# Sound_Sensor_Schematic_Rev1.net
KiCad netlist of a schematic drawn in EAGLE
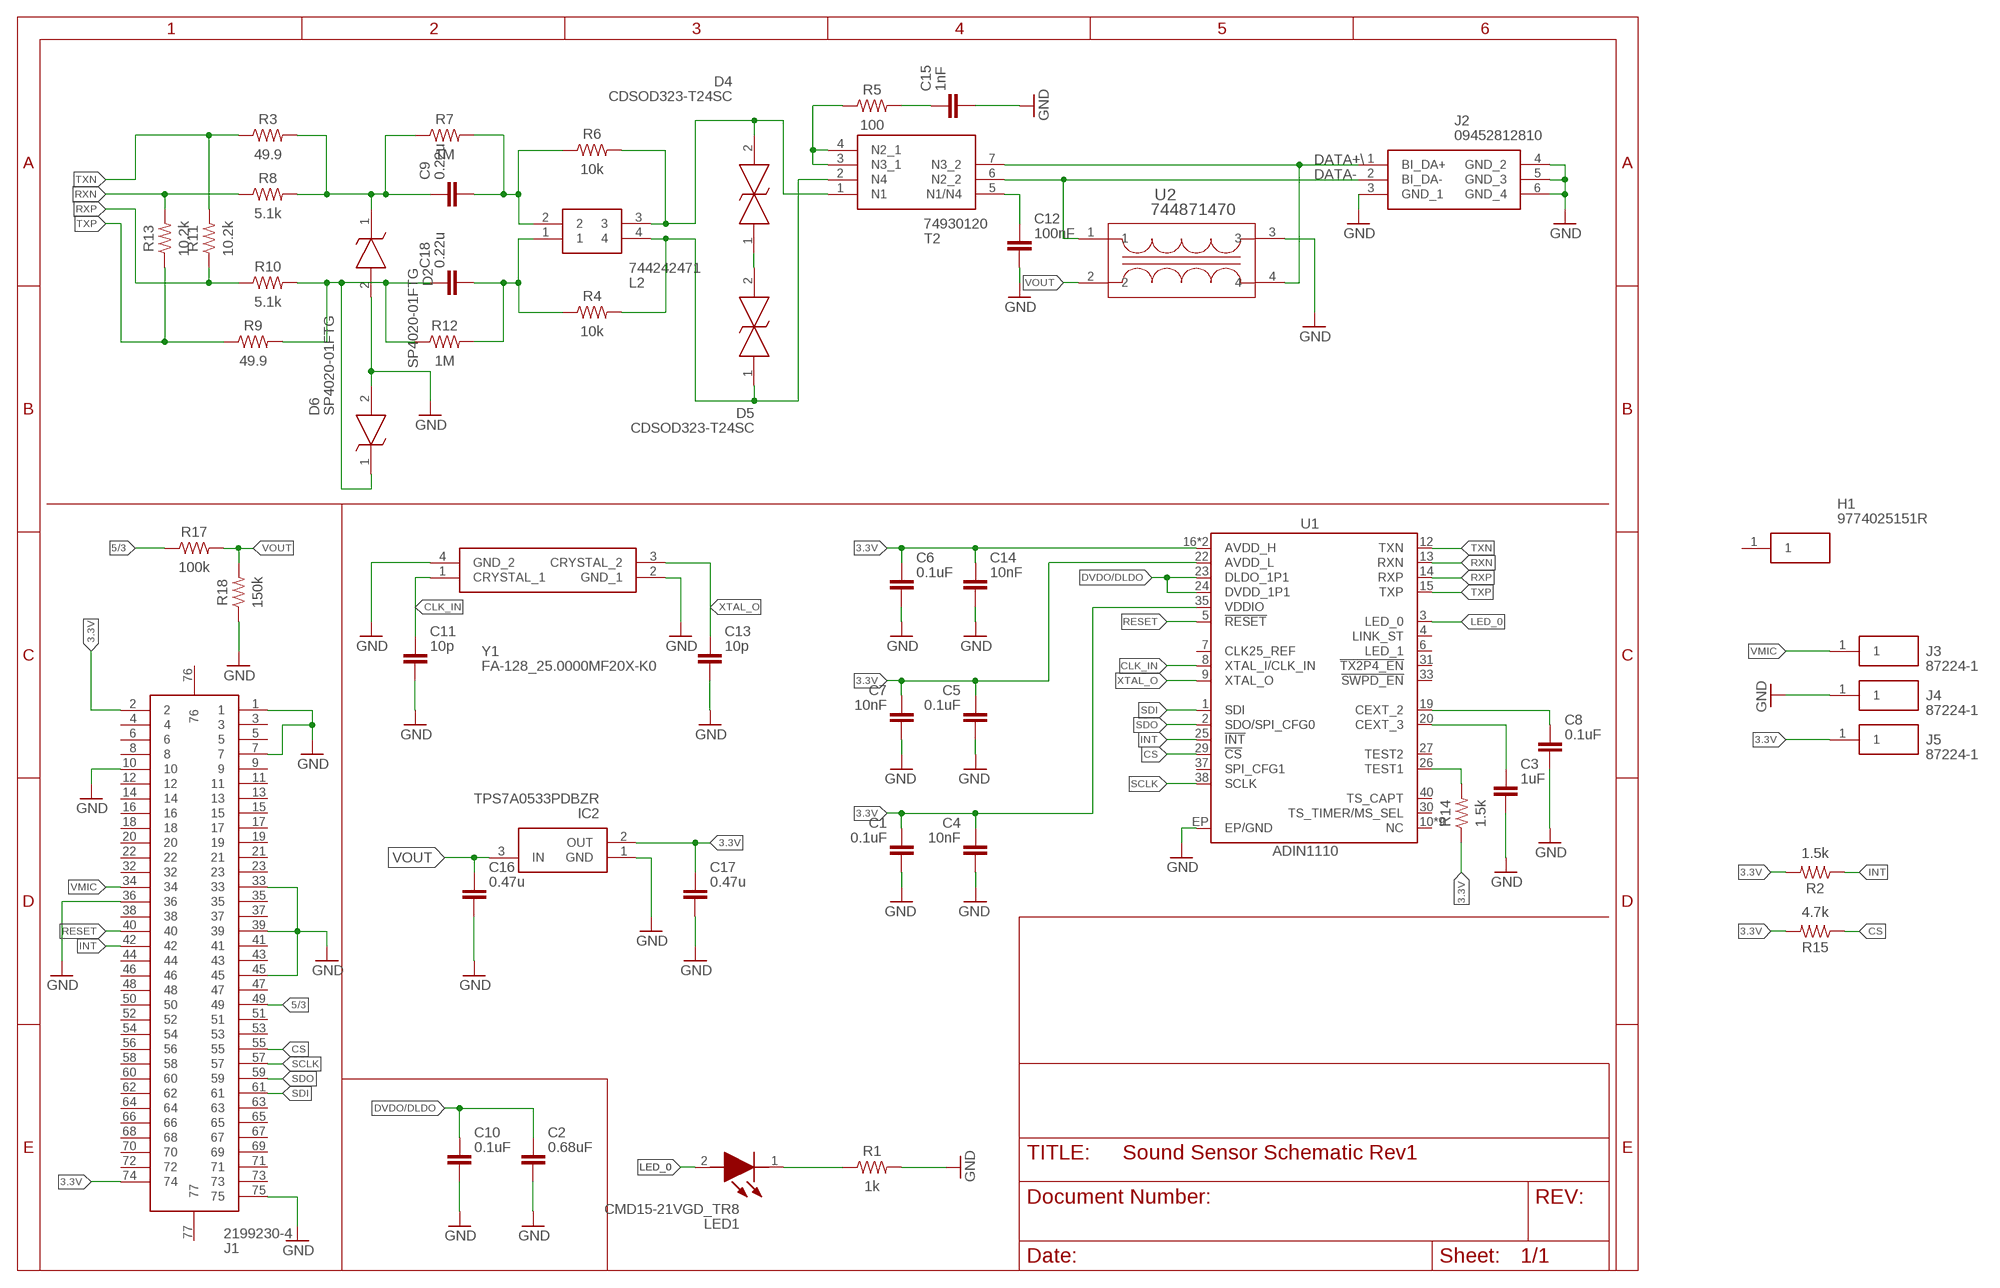
[diagram p0: schematic, sheet 1]

(export (version "E")
  (design (tool "Eeschema 10.0.6"))
  (components
    (comp (ref "C1")
      (value "0.1uF")
      (footprint "eagle-import:CAPC1005X60")
      (libsource (lib "eagle-import") (part "CCHIP-0402(1005-METRIC)_"))
    )
    (comp (ref "C2")
      (value "0.68uF")
      (footprint "eagle-import:CAPC1005X60")
      (libsource (lib "eagle-import") (part "CCHIP-0402(1005-METRIC)_"))
    )
    (comp (ref "C3")
      (value "1uF")
      (footprint "eagle-import:CAPC1005X60")
      (libsource (lib "eagle-import") (part "CCHIP-0402(1005-METRIC)_"))
    )
    (comp (ref "C4")
      (value "10nF")
      (footprint "eagle-import:CAPC1005X60")
      (libsource (lib "eagle-import") (part "CCHIP-0402(1005-METRIC)_"))
    )
    (comp (ref "C5")
      (value "0.1uF")
      (footprint "eagle-import:CAPC1005X60")
      (libsource (lib "eagle-import") (part "CCHIP-0402(1005-METRIC)_"))
    )
    (comp (ref "C6")
      (value "0.1uF")
      (footprint "eagle-import:CAPC1005X60")
      (libsource (lib "eagle-import") (part "CCHIP-0402(1005-METRIC)_"))
    )
    (comp (ref "C7")
      (value "10nF")
      (footprint "eagle-import:CAPC1005X60")
      (libsource (lib "eagle-import") (part "CCHIP-0402(1005-METRIC)_"))
    )
    (comp (ref "C8")
      (value "0.1uF")
      (footprint "eagle-import:CAPC1005X60")
      (libsource (lib "eagle-import") (part "CCHIP-0402(1005-METRIC)_"))
    )
    (comp (ref "C9")
      (value "0.22u")
      (footprint "eagle-import:CAPC1005X60")
      (libsource (lib "eagle-import") (part "CCHIP-0402(1005-METRIC)_"))
    )
    (comp (ref "C10")
      (value "0.1uF")
      (footprint "eagle-import:CAPC1005X60")
      (libsource (lib "eagle-import") (part "CCHIP-0402(1005-METRIC)_"))
    )
    (comp (ref "C11")
      (value "10p")
      (footprint "eagle-import:CAPC1005X60")
      (libsource (lib "eagle-import") (part "CCHIP-0402(1005-METRIC)_"))
    )
    (comp (ref "C12")
      (value "100nF")
      (footprint "eagle-import:CAPC1005X60")
      (libsource (lib "eagle-import") (part "CCHIP-0402(1005-METRIC)_"))
    )
    (comp (ref "C13")
      (value "10p")
      (footprint "eagle-import:CAPC1005X60")
      (libsource (lib "eagle-import") (part "CCHIP-0402(1005-METRIC)_"))
    )
    (comp (ref "C14")
      (value "10nF")
      (footprint "eagle-import:CAPC1005X60")
      (libsource (lib "eagle-import") (part "CCHIP-0402(1005-METRIC)_"))
    )
    (comp (ref "C15")
      (value "1nF")
      (footprint "eagle-import:CAPC1005X60")
      (libsource (lib "eagle-import") (part "CCHIP-0402(1005-METRIC)_"))
    )
    (comp (ref "C16")
      (value "0.47u")
      (footprint "eagle-import:CAPC1005X60")
      (libsource (lib "eagle-import") (part "CCHIP-0402(1005-METRIC)_"))
    )
    (comp (ref "C17")
      (value "0.47u")
      (footprint "eagle-import:CAPC1005X60")
      (libsource (lib "eagle-import") (part "CCHIP-0402(1005-METRIC)_"))
    )
    (comp (ref "C18")
      (value "0.22u")
      (footprint "eagle-import:CAPC1005X60")
      (libsource (lib "eagle-import") (part "CCHIP-0402(1005-METRIC)_"))
    )
    (comp (ref "D2")
      (value "SP4020-01FTG")
      (footprint "eagle-import:SOD2613X114N")
      (fields (field (name "MOUSER_PART_NUMBER") "576-SP4020-01FTG"))
      (libsource (lib "eagle-import") (part "SP4020-01FTG"))
    )
    (comp (ref "D4")
      (value "CDSOD323-T24SC")
      (footprint "eagle-import:SOD2513X114N")
      (fields (field (name "MOUSER_PART_NUMBER") "652-CDSOD323-T24SC"))
      (libsource (lib "eagle-import") (part "CDSOD323-T24SC"))
    )
    (comp (ref "D5")
      (value "CDSOD323-T24SC")
      (footprint "eagle-import:SOD2513X114N")
      (fields (field (name "MOUSER_PART_NUMBER") "652-CDSOD323-T24SC"))
      (libsource (lib "eagle-import") (part "CDSOD323-T24SC"))
    )
    (comp (ref "D6")
      (value "SP4020-01FTG")
      (footprint "eagle-import:SOD2613X114N")
      (fields (field (name "MOUSER_PART_NUMBER") "576-SP4020-01FTG"))
      (libsource (lib "eagle-import") (part "SP4020-01FTG"))
    )
    (comp (ref "H1")
      (value "9774025151R")
      (footprint "eagle-import:9774025151R")
      (fields (field (name "MOUSER_PART_NUMBER") "710-9774025151R"))
      (libsource (lib "eagle-import") (part "9774025151R"))
    )
    (comp (ref "IC2")
      (value "TPS7A0533PDBZR")
      (footprint "eagle-import:SOT95P237X112-3N")
      (fields (field (name "MOUSER_PART_NUMBER") "595-TPS7A0533PDBZR"))
      (libsource (lib "eagle-import") (part "TPS7A0533PDBZR"))
    )
    (comp (ref "J1")
      (value "2199230-4")
      (footprint "eagle-import:21992304")
      (fields (field (name "MOUSER_PART_NUMBER") "571-2199230-4"))
      (libsource (lib "eagle-import") (part "2199230-4"))
    )
    (comp (ref "J2")
      (value "09452812810")
      (footprint "eagle-import:09452812810")
      (fields (field (name "MOUSER_PART_NUMBER") "617-09452812810"))
      (libsource (lib "eagle-import") (part "09452812810"))
    )
    (comp (ref "J3")
      (value "87224-1")
      (footprint "eagle-import:HDRV1W66P0X254_1X1_213X254X107")
      (fields (field (name "MOUSER_PART_NUMBER") "571-872241"))
      (libsource (lib "eagle-import") (part "87224-1"))
    )
    (comp (ref "J4")
      (value "87224-1")
      (footprint "eagle-import:HDRV1W66P0X254_1X1_213X254X107")
      (fields (field (name "MOUSER_PART_NUMBER") "571-872241"))
      (libsource (lib "eagle-import") (part "87224-1"))
    )
    (comp (ref "J5")
      (value "87224-1")
      (footprint "eagle-import:HDRV1W66P0X254_1X1_213X254X107")
      (fields (field (name "MOUSER_PART_NUMBER") "571-872241"))
      (libsource (lib "eagle-import") (part "87224-1"))
    )
    (comp (ref "L2")
      (value "744242471")
      (footprint "eagle-import:744242471")
      (fields (field (name "MOUSER_PART_NUMBER") "710-744242471"))
      (libsource (lib "eagle-import") (part "744242471"))
    )
    (comp (ref "LED1")
      (value "CMD15-21VGD_TR8")
      (footprint "eagle-import:LEDC3215X130N")
      (fields
        (field (name "ARROW_PART_NUMBER") "CMD15-21VGD/TR8")
        (field (name "MOUSER_PART_NUMBER") "606-CMD15-21VGD/TR8")
      )
      (libsource (lib "eagle-import") (part "CMD15-21VGD_TR8"))
    )
    (comp (ref "R1")
      (value "1k")
      (footprint "eagle-import:RESC1005X40")
      (libsource (lib "eagle-import") (part "R-USCHIP-0402(1005-METRIC)_"))
    )
    (comp (ref "R2")
      (value "1.5k")
      (footprint "eagle-import:RESC1005X40")
      (libsource (lib "eagle-import") (part "R-USCHIP-0402(1005-METRIC)_"))
    )
    (comp (ref "R3")
      (value "49.9")
      (footprint "eagle-import:RESC1005X40")
      (libsource (lib "eagle-import") (part "R-USCHIP-0402(1005-METRIC)_"))
    )
    (comp (ref "R4")
      (value "10k")
      (footprint "eagle-import:RESC1005X40")
      (libsource (lib "eagle-import") (part "R-USCHIP-0402(1005-METRIC)_"))
    )
    (comp (ref "R5")
      (value "100")
      (footprint "eagle-import:RESC1005X40")
      (libsource (lib "eagle-import") (part "R-USCHIP-0402(1005-METRIC)_"))
    )
    (comp (ref "R6")
      (value "10k")
      (footprint "eagle-import:RESC1005X40")
      (libsource (lib "eagle-import") (part "R-USCHIP-0402(1005-METRIC)_"))
    )
    (comp (ref "R7")
      (value "1M")
      (footprint "eagle-import:RESC1005X40")
      (libsource (lib "eagle-import") (part "R-USCHIP-0402(1005-METRIC)_"))
    )
    (comp (ref "R8")
      (value "5.1k")
      (footprint "eagle-import:RESC1005X40")
      (libsource (lib "eagle-import") (part "R-USCHIP-0402(1005-METRIC)_"))
    )
    (comp (ref "R9")
      (value "49.9")
      (footprint "eagle-import:RESC1005X40")
      (libsource (lib "eagle-import") (part "R-USCHIP-0402(1005-METRIC)_"))
    )
    (comp (ref "R10")
      (value "5.1k")
      (footprint "eagle-import:RESC1005X40")
      (libsource (lib "eagle-import") (part "R-USCHIP-0402(1005-METRIC)_"))
    )
    (comp (ref "R11")
      (value "10.2k")
      (footprint "eagle-import:RESC1005X40")
      (libsource (lib "eagle-import") (part "R-USCHIP-0402(1005-METRIC)_"))
    )
    (comp (ref "R12")
      (value "1M")
      (footprint "eagle-import:RESC1005X40")
      (libsource (lib "eagle-import") (part "R-USCHIP-0402(1005-METRIC)_"))
    )
    (comp (ref "R13")
      (value "10.2k")
      (footprint "eagle-import:RESC1005X40")
      (libsource (lib "eagle-import") (part "R-USCHIP-0402(1005-METRIC)_"))
    )
    (comp (ref "R14")
      (value "1.5k")
      (footprint "eagle-import:RESC1005X40")
      (libsource (lib "eagle-import") (part "R-USCHIP-0402(1005-METRIC)_"))
    )
    (comp (ref "R15")
      (value "4.7k")
      (footprint "eagle-import:RESC1005X40")
      (libsource (lib "eagle-import") (part "R-USCHIP-0402(1005-METRIC)_"))
    )
    (comp (ref "R17")
      (value "100k")
      (footprint "eagle-import:RESC1005X40")
      (libsource (lib "eagle-import") (part "R-USCHIP-0402(1005-METRIC)_"))
    )
    (comp (ref "R18")
      (value "150k")
      (footprint "eagle-import:RESC1005X40")
      (libsource (lib "eagle-import") (part "R-USCHIP-0402(1005-METRIC)_"))
    )
    (comp (ref "T2")
      (value "74930120")
      (footprint "eagle-import:74930120")
      (fields (field (name "MOUSER_PART_NUMBER") "710-74930120"))
      (libsource (lib "eagle-import") (part "74930120"))
    )
    (comp (ref "U1")
      (value "ADIN1110")
      (footprint "eagle-import:LFCSP-40")
      (libsource (lib "eagle-import") (part "ADIN1110"))
    )
    (comp (ref "U2")
      (value "744871470")
      (footprint "eagle-import:SMT_871470_WRE")
      (fields (field (name "COPYRIGHT") "Copyright (C) 2023 Ultra Librarian. All rights reserved."))
      (libsource (lib "eagle-import") (part "744871470"))
    )
    (comp (ref "Y1")
      (value "FA-128_25.0000MF20X-K0")
      (footprint "eagle-import:FA128250000MF20XK0")
      (fields
        (field (name "MANUFACTURER_PART_NUMBER") "FA-128 25.0000MF20X-K0")
        (field (name "MOUSER_PART_NUMBER") "732-FA-12825F20X-K0")
      )
      (libsource (lib "eagle-import") (part "FA-128_25.0000MF20X-K0"))
    )
  )
  (nets
    (net (code "1") (name "/DATA+\\") (class "Default")
      (node (ref "J2") (pin "1") (pinfunction "BI_DA+_1") (pintype "bidirectional"))
      (node (ref "T2") (pin "7") (pinfunction "N3_2_7") (pintype "bidirectional"))
      (node (ref "U2") (pin "4") (pinfunction "4_4") (pintype "passive"))
    )
    (net (code "2") (name "/DATA-") (class "Default")
      (node (ref "J2") (pin "2") (pinfunction "BI_DA-_2") (pintype "bidirectional"))
      (node (ref "T2") (pin "6") (pinfunction "N2_2_6") (pintype "bidirectional"))
      (node (ref "U2") (pin "1") (pinfunction "1_1") (pintype "passive"))
    )
    (net (code "3") (name "3.3V") (class "Default")
      (node (ref "C1") (pin "1") (pinfunction "1_1") (pintype "passive"))
      (node (ref "C14") (pin "1") (pinfunction "1_1") (pintype "passive"))
      (node (ref "C17") (pin "1") (pinfunction "1_1") (pintype "passive"))
      (node (ref "C4") (pin "1") (pinfunction "1_1") (pintype "passive"))
      (node (ref "C5") (pin "1") (pinfunction "1_1") (pintype "passive"))
      (node (ref "C6") (pin "1") (pinfunction "1_1") (pintype "passive"))
      (node (ref "C7") (pin "1") (pinfunction "1_1") (pintype "passive"))
      (node (ref "IC2") (pin "2") (pinfunction "OUT_2") (pintype "output"))
      (node (ref "J1") (pin "2") (pinfunction "2_2") (pintype "bidirectional"))
      (node (ref "J1") (pin "74") (pinfunction "74_74") (pintype "bidirectional"))
      (node (ref "J5") (pin "1") (pinfunction "1_1") (pintype "bidirectional"))
      (node (ref "R14") (pin "1") (pinfunction "1_1") (pintype "passive"))
      (node (ref "R15") (pin "2") (pinfunction "2_2") (pintype "passive"))
      (node (ref "R2") (pin "2") (pinfunction "2_2") (pintype "passive"))
      (node (ref "U1") (pin "16") (pinfunction "AVDD_H_16") (pintype "bidirectional"))
      (node (ref "U1") (pin "17") (pinfunction "AVDD_H_17") (pintype "bidirectional"))
      (node (ref "U1") (pin "22") (pinfunction "AVDD_L_22") (pintype "bidirectional"))
      (node (ref "U1") (pin "35") (pinfunction "VDDIO_35") (pintype "bidirectional"))
    )
    (net (code "4") (name "5{slash}3") (class "Default")
      (node (ref "J1") (pin "49") (pinfunction "49_49") (pintype "bidirectional"))
      (node (ref "R17") (pin "1") (pinfunction "1_1") (pintype "passive"))
    )
    (net (code "5") (name "CLK_IN") (class "Default")
      (node (ref "C11") (pin "1") (pinfunction "1_1") (pintype "passive"))
      (node (ref "U1") (pin "8") (pinfunction "XTAL_I/CLK_IN_8") (pintype "bidirectional"))
      (node (ref "Y1") (pin "1") (pinfunction "CRYSTAL_1_1") (pintype "bidirectional"))
    )
    (net (code "6") (name "CS") (class "Default")
      (node (ref "J1") (pin "55") (pinfunction "55_55") (pintype "bidirectional"))
      (node (ref "R15") (pin "1") (pinfunction "1_1") (pintype "passive"))
      (node (ref "U1") (pin "29") (pinfunction "~{CS}_29") (pintype "bidirectional"))
    )
    (net (code "7") (name "DVDO{slash}DLDO") (class "Default")
      (node (ref "C10") (pin "1") (pinfunction "1_1") (pintype "passive"))
      (node (ref "C2") (pin "1") (pinfunction "1_1") (pintype "passive"))
      (node (ref "U1") (pin "23") (pinfunction "DLDO_1P1_23") (pintype "bidirectional"))
      (node (ref "U1") (pin "24") (pinfunction "DVDD_1P1_24") (pintype "bidirectional"))
    )
    (net (code "8") (name "GND") (class "Default")
      (node (ref "C1") (pin "2") (pinfunction "2_2") (pintype "passive"))
      (node (ref "C10") (pin "2") (pinfunction "2_2") (pintype "passive"))
      (node (ref "C11") (pin "2") (pinfunction "2_2") (pintype "passive"))
      (node (ref "C12") (pin "2") (pinfunction "2_2") (pintype "passive"))
      (node (ref "C13") (pin "2") (pinfunction "2_2") (pintype "passive"))
      (node (ref "C14") (pin "2") (pinfunction "2_2") (pintype "passive"))
      (node (ref "C15") (pin "2") (pinfunction "2_2") (pintype "passive"))
      (node (ref "C16") (pin "2") (pinfunction "2_2") (pintype "passive"))
      (node (ref "C17") (pin "2") (pinfunction "2_2") (pintype "passive"))
      (node (ref "C2") (pin "2") (pinfunction "2_2") (pintype "passive"))
      (node (ref "C3") (pin "2") (pinfunction "2_2") (pintype "passive"))
      (node (ref "C4") (pin "2") (pinfunction "2_2") (pintype "passive"))
      (node (ref "C5") (pin "2") (pinfunction "2_2") (pintype "passive"))
      (node (ref "C6") (pin "2") (pinfunction "2_2") (pintype "passive"))
      (node (ref "C7") (pin "2") (pinfunction "2_2") (pintype "passive"))
      (node (ref "C8") (pin "2") (pinfunction "2_2") (pintype "passive"))
      (node (ref "D2") (pin "2") (pinfunction "A_2") (pintype "bidirectional"))
      (node (ref "D6") (pin "2") (pinfunction "A_2") (pintype "bidirectional"))
      (node (ref "IC2") (pin "1") (pinfunction "GND_1") (pintype "power_in"))
      (node (ref "J1") (pin "1") (pinfunction "1_1") (pintype "bidirectional"))
      (node (ref "J1") (pin "10") (pinfunction "10_10") (pintype "bidirectional"))
      (node (ref "J1") (pin "33") (pinfunction "33_33") (pintype "bidirectional"))
      (node (ref "J1") (pin "36") (pinfunction "36_36") (pintype "bidirectional"))
      (node (ref "J1") (pin "39") (pinfunction "39_39") (pintype "bidirectional"))
      (node (ref "J1") (pin "45") (pinfunction "45_45") (pintype "bidirectional"))
      (node (ref "J1") (pin "7") (pinfunction "7_7") (pintype "bidirectional"))
      (node (ref "J1") (pin "75") (pinfunction "75_75") (pintype "bidirectional"))
      (node (ref "J2") (pin "3") (pinfunction "GND_1_3") (pintype "bidirectional"))
      (node (ref "J2") (pin "4") (pinfunction "GND_2_4") (pintype "bidirectional"))
      (node (ref "J2") (pin "5") (pinfunction "GND_3_5") (pintype "bidirectional"))
      (node (ref "J2") (pin "6") (pinfunction "GND_4_6") (pintype "bidirectional"))
      (node (ref "J4") (pin "1") (pinfunction "1_1") (pintype "bidirectional"))
      (node (ref "R1") (pin "2") (pinfunction "2_2") (pintype "passive"))
      (node (ref "R18") (pin "1") (pinfunction "1_1") (pintype "passive"))
      (node (ref "U1") (pin "EP") (pinfunction "EP/GND_EP") (pintype "bidirectional"))
      (node (ref "U2") (pin "3") (pinfunction "3_3") (pintype "passive"))
      (node (ref "Y1") (pin "2") (pinfunction "GND_1_2") (pintype "bidirectional"))
      (node (ref "Y1") (pin "4") (pinfunction "GND_2_4") (pintype "bidirectional"))
    )
    (net (code "9") (name "INT") (class "Default")
      (node (ref "J1") (pin "42") (pinfunction "42_42") (pintype "bidirectional"))
      (node (ref "R2") (pin "1") (pinfunction "1_1") (pintype "passive"))
      (node (ref "U1") (pin "25") (pinfunction "~{INT}_25") (pintype "bidirectional"))
    )
    (net (code "10") (name "LED_0") (class "Default")
      (node (ref "LED1") (pin "2") (pinfunction "A_2") (pintype "bidirectional"))
      (node (ref "U1") (pin "3") (pinfunction "LED_0_3") (pintype "bidirectional"))
    )
    (net (code "11") (name "Net-(C9-Pad2)") (class "Default")
      (node (ref "C9") (pin "2") (pinfunction "2_2") (pintype "passive"))
      (node (ref "L2") (pin "2") (pinfunction "2_2") (pintype "bidirectional"))
      (node (ref "R6") (pin "1") (pinfunction "1_1") (pintype "passive"))
      (node (ref "R7") (pin "2") (pinfunction "2_2") (pintype "passive"))
    )
    (net (code "12") (name "Net-(C15-Pad1)") (class "Default")
      (node (ref "C15") (pin "1") (pinfunction "1_1") (pintype "passive"))
      (node (ref "R5") (pin "2") (pinfunction "2_2") (pintype "passive"))
    )
    (net (code "13") (name "Net-(C18-Pad2)") (class "Default")
      (node (ref "C18") (pin "2") (pinfunction "2_2") (pintype "passive"))
      (node (ref "L2") (pin "1") (pinfunction "1_1") (pintype "bidirectional"))
      (node (ref "R12") (pin "2") (pinfunction "2_2") (pintype "passive"))
      (node (ref "R4") (pin "1") (pinfunction "1_1") (pintype "passive"))
    )
    (net (code "14") (name "Net-(D2-K)") (class "Default")
      (node (ref "C9") (pin "1") (pinfunction "1_1") (pintype "passive"))
      (node (ref "D2") (pin "1") (pinfunction "K_1") (pintype "bidirectional"))
      (node (ref "R3") (pin "2") (pinfunction "2_2") (pintype "passive"))
      (node (ref "R7") (pin "1") (pinfunction "1_1") (pintype "passive"))
      (node (ref "R8") (pin "2") (pinfunction "2_2") (pintype "passive"))
    )
    (net (code "15") (name "Net-(D4-Pad1)") (class "Default")
      (node (ref "D4") (pin "1") (pinfunction "1_1") (pintype "bidirectional"))
      (node (ref "D5") (pin "2") (pinfunction "2_2") (pintype "bidirectional"))
    )
    (net (code "16") (name "Net-(D6-K)") (class "Default")
      (node (ref "C18") (pin "1") (pinfunction "1_1") (pintype "passive"))
      (node (ref "D6") (pin "1") (pinfunction "K_1") (pintype "bidirectional"))
      (node (ref "R10") (pin "2") (pinfunction "2_2") (pintype "passive"))
      (node (ref "R12") (pin "1") (pinfunction "1_1") (pintype "passive"))
      (node (ref "R9") (pin "2") (pinfunction "2_2") (pintype "passive"))
    )
    (net (code "17") (name "Net-(LED1-K)") (class "Default")
      (node (ref "LED1") (pin "1") (pinfunction "K_1") (pintype "bidirectional"))
      (node (ref "R1") (pin "1") (pinfunction "1_1") (pintype "passive"))
    )
    (net (code "18") (name "Net-(T2-N1)") (class "Default")
      (node (ref "D4") (pin "2") (pinfunction "2_2") (pintype "bidirectional"))
      (node (ref "L2") (pin "3") (pinfunction "3_3") (pintype "bidirectional"))
      (node (ref "R6") (pin "2") (pinfunction "2_2") (pintype "passive"))
      (node (ref "T2") (pin "1") (pinfunction "N1_1") (pintype "bidirectional"))
    )
    (net (code "19") (name "Net-(T2-N1{slash}N4)") (class "Default")
      (node (ref "C12") (pin "1") (pinfunction "1_1") (pintype "passive"))
      (node (ref "T2") (pin "5") (pinfunction "N1/N4_5") (pintype "bidirectional"))
    )
    (net (code "20") (name "Net-(T2-N2_1)") (class "Default")
      (node (ref "R5") (pin "1") (pinfunction "1_1") (pintype "passive"))
      (node (ref "T2") (pin "3") (pinfunction "N3_1_3") (pintype "bidirectional"))
      (node (ref "T2") (pin "4") (pinfunction "N2_1_4") (pintype "bidirectional"))
    )
    (net (code "21") (name "Net-(T2-N4)") (class "Default")
      (node (ref "D5") (pin "1") (pinfunction "1_1") (pintype "bidirectional"))
      (node (ref "L2") (pin "4") (pinfunction "4_4") (pintype "bidirectional"))
      (node (ref "R4") (pin "2") (pinfunction "2_2") (pintype "passive"))
      (node (ref "T2") (pin "2") (pinfunction "N4_2") (pintype "bidirectional"))
    )
    (net (code "22") (name "Net-(U1-CEXT_2)") (class "Default")
      (node (ref "C8") (pin "1") (pinfunction "1_1") (pintype "passive"))
      (node (ref "U1") (pin "19") (pinfunction "CEXT_2_19") (pintype "bidirectional"))
    )
    (net (code "23") (name "Net-(U1-CEXT_3)") (class "Default")
      (node (ref "C3") (pin "1") (pinfunction "1_1") (pintype "passive"))
      (node (ref "U1") (pin "20") (pinfunction "CEXT_3_20") (pintype "bidirectional"))
    )
    (net (code "24") (name "Net-(U1-TEST1)") (class "Default")
      (node (ref "R14") (pin "2") (pinfunction "2_2") (pintype "passive"))
      (node (ref "U1") (pin "26") (pinfunction "TEST1_26") (pintype "bidirectional"))
    )
    (net (code "25") (name "RESET") (class "Default")
      (node (ref "J1") (pin "40") (pinfunction "40_40") (pintype "bidirectional"))
      (node (ref "U1") (pin "5") (pinfunction "~{RESET}_5") (pintype "bidirectional"))
    )
    (net (code "26") (name "RXN") (class "Default")
      (node (ref "R13") (pin "2") (pinfunction "2_2") (pintype "passive"))
      (node (ref "R8") (pin "1") (pinfunction "1_1") (pintype "passive"))
      (node (ref "U1") (pin "13") (pinfunction "RXN_13") (pintype "bidirectional"))
    )
    (net (code "27") (name "RXP") (class "Default")
      (node (ref "R10") (pin "1") (pinfunction "1_1") (pintype "passive"))
      (node (ref "R11") (pin "1") (pinfunction "1_1") (pintype "passive"))
      (node (ref "U1") (pin "14") (pinfunction "RXP_14") (pintype "bidirectional"))
    )
    (net (code "28") (name "SCLK") (class "Default")
      (node (ref "J1") (pin "57") (pinfunction "57_57") (pintype "bidirectional"))
      (node (ref "U1") (pin "38") (pinfunction "SCLK_38") (pintype "bidirectional"))
    )
    (net (code "29") (name "SDI") (class "Default")
      (node (ref "J1") (pin "61") (pinfunction "61_61") (pintype "bidirectional"))
      (node (ref "U1") (pin "1") (pinfunction "SDI_1") (pintype "bidirectional"))
    )
    (net (code "30") (name "SDO") (class "Default")
      (node (ref "J1") (pin "59") (pinfunction "59_59") (pintype "bidirectional"))
      (node (ref "U1") (pin "2") (pinfunction "SDO/SPI_CFG0_2") (pintype "bidirectional"))
    )
    (net (code "31") (name "TXN") (class "Default")
      (node (ref "R11") (pin "2") (pinfunction "2_2") (pintype "passive"))
      (node (ref "R3") (pin "1") (pinfunction "1_1") (pintype "passive"))
      (node (ref "U1") (pin "12") (pinfunction "TXN_12") (pintype "bidirectional"))
    )
    (net (code "32") (name "TXP") (class "Default")
      (node (ref "R13") (pin "1") (pinfunction "1_1") (pintype "passive"))
      (node (ref "R9") (pin "1") (pinfunction "1_1") (pintype "passive"))
      (node (ref "U1") (pin "15") (pinfunction "TXP_15") (pintype "bidirectional"))
    )
    (net (code "33") (name "VMIC") (class "Default")
      (node (ref "J1") (pin "34") (pinfunction "34_34") (pintype "bidirectional"))
      (node (ref "J3") (pin "1") (pinfunction "1_1") (pintype "bidirectional"))
    )
    (net (code "34") (name "VOUT") (class "Default")
      (node (ref "C16") (pin "1") (pinfunction "1_1") (pintype "passive"))
      (node (ref "IC2") (pin "3") (pinfunction "IN_3") (pintype "input"))
      (node (ref "R17") (pin "2") (pinfunction "2_2") (pintype "passive"))
      (node (ref "R18") (pin "2") (pinfunction "2_2") (pintype "passive"))
      (node (ref "U2") (pin "2") (pinfunction "2_2") (pintype "passive"))
    )
    (net (code "35") (name "XTAL_O") (class "Default")
      (node (ref "C13") (pin "1") (pinfunction "1_1") (pintype "passive"))
      (node (ref "U1") (pin "9") (pinfunction "XTAL_O_9") (pintype "bidirectional"))
      (node (ref "Y1") (pin "3") (pinfunction "CRYSTAL_2_3") (pintype "bidirectional"))
    )
    (net (code "36") (name "unconnected-(H1-Pad1)") (class "Default")
      (node (ref "H1") (pin "1") (pinfunction "1_1") (pintype "bidirectional"))
    )
    (net (code "37") (name "unconnected-(J1-Pad3)") (class "Default")
      (node (ref "J1") (pin "3") (pinfunction "3_3") (pintype "bidirectional"))
    )
    (net (code "38") (name "unconnected-(J1-Pad4)") (class "Default")
      (node (ref "J1") (pin "4") (pinfunction "4_4") (pintype "bidirectional"))
    )
    (net (code "39") (name "unconnected-(J1-Pad5)") (class "Default")
      (node (ref "J1") (pin "5") (pinfunction "5_5") (pintype "bidirectional"))
    )
    (net (code "40") (name "unconnected-(J1-Pad6)") (class "Default")
      (node (ref "J1") (pin "6") (pinfunction "6_6") (pintype "bidirectional"))
    )
    (net (code "41") (name "unconnected-(J1-Pad8)") (class "Default")
      (node (ref "J1") (pin "8") (pinfunction "8_8") (pintype "bidirectional"))
    )
    (net (code "42") (name "unconnected-(J1-Pad9)") (class "Default")
      (node (ref "J1") (pin "9") (pinfunction "9_9") (pintype "bidirectional"))
    )
    (net (code "43") (name "unconnected-(J1-Pad11)") (class "Default")
      (node (ref "J1") (pin "11") (pinfunction "11_11") (pintype "bidirectional"))
    )
    (net (code "44") (name "unconnected-(J1-Pad12)") (class "Default")
      (node (ref "J1") (pin "12") (pinfunction "12_12") (pintype "bidirectional"))
    )
    (net (code "45") (name "unconnected-(J1-Pad13)") (class "Default")
      (node (ref "J1") (pin "13") (pinfunction "13_13") (pintype "bidirectional"))
    )
    (net (code "46") (name "unconnected-(J1-Pad14)") (class "Default")
      (node (ref "J1") (pin "14") (pinfunction "14_14") (pintype "bidirectional"))
    )
    (net (code "47") (name "unconnected-(J1-Pad15)") (class "Default")
      (node (ref "J1") (pin "15") (pinfunction "15_15") (pintype "bidirectional"))
    )
    (net (code "48") (name "unconnected-(J1-Pad16)") (class "Default")
      (node (ref "J1") (pin "16") (pinfunction "16_16") (pintype "bidirectional"))
    )
    (net (code "49") (name "unconnected-(J1-Pad17)") (class "Default")
      (node (ref "J1") (pin "17") (pinfunction "17_17") (pintype "bidirectional"))
    )
    (net (code "50") (name "unconnected-(J1-Pad18)") (class "Default")
      (node (ref "J1") (pin "18") (pinfunction "18_18") (pintype "bidirectional"))
    )
    (net (code "51") (name "unconnected-(J1-Pad19)") (class "Default")
      (node (ref "J1") (pin "19") (pinfunction "19_19") (pintype "bidirectional"))
    )
    (net (code "52") (name "unconnected-(J1-Pad20)") (class "Default")
      (node (ref "J1") (pin "20") (pinfunction "20_20") (pintype "bidirectional"))
    )
    (net (code "53") (name "unconnected-(J1-Pad21)") (class "Default")
      (node (ref "J1") (pin "21") (pinfunction "21_21") (pintype "bidirectional"))
    )
    (net (code "54") (name "unconnected-(J1-Pad22)") (class "Default")
      (node (ref "J1") (pin "22") (pinfunction "22_22") (pintype "bidirectional"))
    )
    (net (code "55") (name "unconnected-(J1-Pad23)") (class "Default")
      (node (ref "J1") (pin "23") (pinfunction "23_23") (pintype "bidirectional"))
    )
    (net (code "56") (name "unconnected-(J1-Pad32)") (class "Default")
      (node (ref "J1") (pin "32") (pinfunction "32_32") (pintype "bidirectional"))
    )
    (net (code "57") (name "unconnected-(J1-Pad35)") (class "Default")
      (node (ref "J1") (pin "35") (pinfunction "35_35") (pintype "bidirectional"))
    )
    (net (code "58") (name "unconnected-(J1-Pad37)") (class "Default")
      (node (ref "J1") (pin "37") (pinfunction "37_37") (pintype "bidirectional"))
    )
    (net (code "59") (name "unconnected-(J1-Pad38)") (class "Default")
      (node (ref "J1") (pin "38") (pinfunction "38_38") (pintype "bidirectional"))
    )
    (net (code "60") (name "unconnected-(J1-Pad41)") (class "Default")
      (node (ref "J1") (pin "41") (pinfunction "41_41") (pintype "bidirectional"))
    )
    (net (code "61") (name "unconnected-(J1-Pad43)") (class "Default")
      (node (ref "J1") (pin "43") (pinfunction "43_43") (pintype "bidirectional"))
    )
    (net (code "62") (name "unconnected-(J1-Pad44)") (class "Default")
      (node (ref "J1") (pin "44") (pinfunction "44_44") (pintype "bidirectional"))
    )
    (net (code "63") (name "unconnected-(J1-Pad46)") (class "Default")
      (node (ref "J1") (pin "46") (pinfunction "46_46") (pintype "bidirectional"))
    )
    (net (code "64") (name "unconnected-(J1-Pad47)") (class "Default")
      (node (ref "J1") (pin "47") (pinfunction "47_47") (pintype "bidirectional"))
    )
    (net (code "65") (name "unconnected-(J1-Pad48)") (class "Default")
      (node (ref "J1") (pin "48") (pinfunction "48_48") (pintype "bidirectional"))
    )
    (net (code "66") (name "unconnected-(J1-Pad50)") (class "Default")
      (node (ref "J1") (pin "50") (pinfunction "50_50") (pintype "bidirectional"))
    )
    (net (code "67") (name "unconnected-(J1-Pad51)") (class "Default")
      (node (ref "J1") (pin "51") (pinfunction "51_51") (pintype "bidirectional"))
    )
    (net (code "68") (name "unconnected-(J1-Pad52)") (class "Default")
      (node (ref "J1") (pin "52") (pinfunction "52_52") (pintype "bidirectional"))
    )
    (net (code "69") (name "unconnected-(J1-Pad53)") (class "Default")
      (node (ref "J1") (pin "53") (pinfunction "53_53") (pintype "bidirectional"))
    )
    (net (code "70") (name "unconnected-(J1-Pad54)") (class "Default")
      (node (ref "J1") (pin "54") (pinfunction "54_54") (pintype "bidirectional"))
    )
    (net (code "71") (name "unconnected-(J1-Pad56)") (class "Default")
      (node (ref "J1") (pin "56") (pinfunction "56_56") (pintype "bidirectional"))
    )
    (net (code "72") (name "unconnected-(J1-Pad58)") (class "Default")
      (node (ref "J1") (pin "58") (pinfunction "58_58") (pintype "bidirectional"))
    )
    (net (code "73") (name "unconnected-(J1-Pad60)") (class "Default")
      (node (ref "J1") (pin "60") (pinfunction "60_60") (pintype "bidirectional"))
    )
    (net (code "74") (name "unconnected-(J1-Pad62)") (class "Default")
      (node (ref "J1") (pin "62") (pinfunction "62_62") (pintype "bidirectional"))
    )
    (net (code "75") (name "unconnected-(J1-Pad63)") (class "Default")
      (node (ref "J1") (pin "63") (pinfunction "63_63") (pintype "bidirectional"))
    )
    (net (code "76") (name "unconnected-(J1-Pad64)") (class "Default")
      (node (ref "J1") (pin "64") (pinfunction "64_64") (pintype "bidirectional"))
    )
    (net (code "77") (name "unconnected-(J1-Pad65)") (class "Default")
      (node (ref "J1") (pin "65") (pinfunction "65_65") (pintype "bidirectional"))
    )
    (net (code "78") (name "unconnected-(J1-Pad66)") (class "Default")
      (node (ref "J1") (pin "66") (pinfunction "66_66") (pintype "bidirectional"))
    )
    (net (code "79") (name "unconnected-(J1-Pad67)") (class "Default")
      (node (ref "J1") (pin "67") (pinfunction "67_67") (pintype "bidirectional"))
    )
    (net (code "80") (name "unconnected-(J1-Pad68)") (class "Default")
      (node (ref "J1") (pin "68") (pinfunction "68_68") (pintype "bidirectional"))
    )
    (net (code "81") (name "unconnected-(J1-Pad69)") (class "Default")
      (node (ref "J1") (pin "69") (pinfunction "69_69") (pintype "bidirectional"))
    )
    (net (code "82") (name "unconnected-(J1-Pad70)") (class "Default")
      (node (ref "J1") (pin "70") (pinfunction "70_70") (pintype "bidirectional"))
    )
    (net (code "83") (name "unconnected-(J1-Pad71)") (class "Default")
      (node (ref "J1") (pin "71") (pinfunction "71_71") (pintype "bidirectional"))
    )
    (net (code "84") (name "unconnected-(J1-Pad72)") (class "Default")
      (node (ref "J1") (pin "72") (pinfunction "72_72") (pintype "bidirectional"))
    )
    (net (code "85") (name "unconnected-(J1-Pad73)") (class "Default")
      (node (ref "J1") (pin "73") (pinfunction "73_73") (pintype "bidirectional"))
    )
    (net (code "86") (name "unconnected-(J1-Pad76)") (class "Default")
      (node (ref "J1") (pin "76") (pinfunction "76_76") (pintype "bidirectional"))
    )
    (net (code "87") (name "unconnected-(J1-Pad77)") (class "Default")
      (node (ref "J1") (pin "77") (pinfunction "77_77") (pintype "bidirectional"))
    )
    (net (code "88") (name "unconnected-(U1-CLK25_REF-Pad7)") (class "Default")
      (node (ref "U1") (pin "7") (pinfunction "CLK25_REF_7") (pintype "bidirectional"))
    )
    (net (code "89") (name "unconnected-(U1-LED_1-Pad6)") (class "Default")
      (node (ref "U1") (pin "6") (pinfunction "LED_1_6") (pintype "bidirectional"))
    )
    (net (code "90") (name "unconnected-(U1-LINK_ST-Pad4)") (class "Default")
      (node (ref "U1") (pin "4") (pinfunction "LINK_ST_4") (pintype "bidirectional"))
    )
    (net (code "91") (name "unconnected-(U1-NC-Pad10)") (class "Default")
      (node (ref "U1") (pin "10") (pinfunction "NC_10") (pintype "no_connect"))
    )
    (net (code "92") (name "unconnected-(U1-NC-Pad11)") (class "Default")
      (node (ref "U1") (pin "11") (pinfunction "NC_11") (pintype "no_connect"))
    )
    (net (code "93") (name "unconnected-(U1-NC-Pad18)") (class "Default")
      (node (ref "U1") (pin "18") (pinfunction "NC_18") (pintype "no_connect"))
    )
    (net (code "94") (name "unconnected-(U1-NC-Pad21)") (class "Default")
      (node (ref "U1") (pin "21") (pinfunction "NC_21") (pintype "no_connect"))
    )
    (net (code "95") (name "unconnected-(U1-NC-Pad28)") (class "Default")
      (node (ref "U1") (pin "28") (pinfunction "NC_28") (pintype "no_connect"))
    )
    (net (code "96") (name "unconnected-(U1-NC-Pad32)") (class "Default")
      (node (ref "U1") (pin "32") (pinfunction "NC_32") (pintype "no_connect"))
    )
    (net (code "97") (name "unconnected-(U1-NC-Pad34)") (class "Default")
      (node (ref "U1") (pin "34") (pinfunction "NC_34") (pintype "no_connect"))
    )
    (net (code "98") (name "unconnected-(U1-NC-Pad36)") (class "Default")
      (node (ref "U1") (pin "36") (pinfunction "NC_36") (pintype "no_connect"))
    )
    (net (code "99") (name "unconnected-(U1-NC-Pad39)") (class "Default")
      (node (ref "U1") (pin "39") (pinfunction "NC_39") (pintype "no_connect"))
    )
    (net (code "100") (name "unconnected-(U1-SPI_CFG1-Pad37)") (class "Default")
      (node (ref "U1") (pin "37") (pinfunction "SPI_CFG1_37") (pintype "bidirectional"))
    )
    (net (code "101") (name "unconnected-(U1-TEST2-Pad27)") (class "Default")
      (node (ref "U1") (pin "27") (pinfunction "TEST2_27") (pintype "bidirectional"))
    )
    (net (code "102") (name "unconnected-(U1-TS_CAPT-Pad40)") (class "Default")
      (node (ref "U1") (pin "40") (pinfunction "TS_CAPT_40") (pintype "bidirectional"))
    )
    (net (code "103") (name "unconnected-(U1-TS_TIMER{slash}MS_SEL-Pad30)") (class "Default")
      (node (ref "U1") (pin "30") (pinfunction "TS_TIMER/MS_SEL_30") (pintype "bidirectional"))
    )
    (net (code "104") (name "unconnected-(U1-~{SWPD_EN}-Pad33)") (class "Default")
      (node (ref "U1") (pin "33") (pinfunction "~{SWPD_EN}_33") (pintype "bidirectional"))
    )
    (net (code "105") (name "unconnected-(U1-~{TX2P4_EN}-Pad31)") (class "Default")
      (node (ref "U1") (pin "31") (pinfunction "~{TX2P4_EN}_31") (pintype "bidirectional"))
    )
  )
)
